# Sheet1.net
KiCad netlist of a schematic drawn in Altium Designer
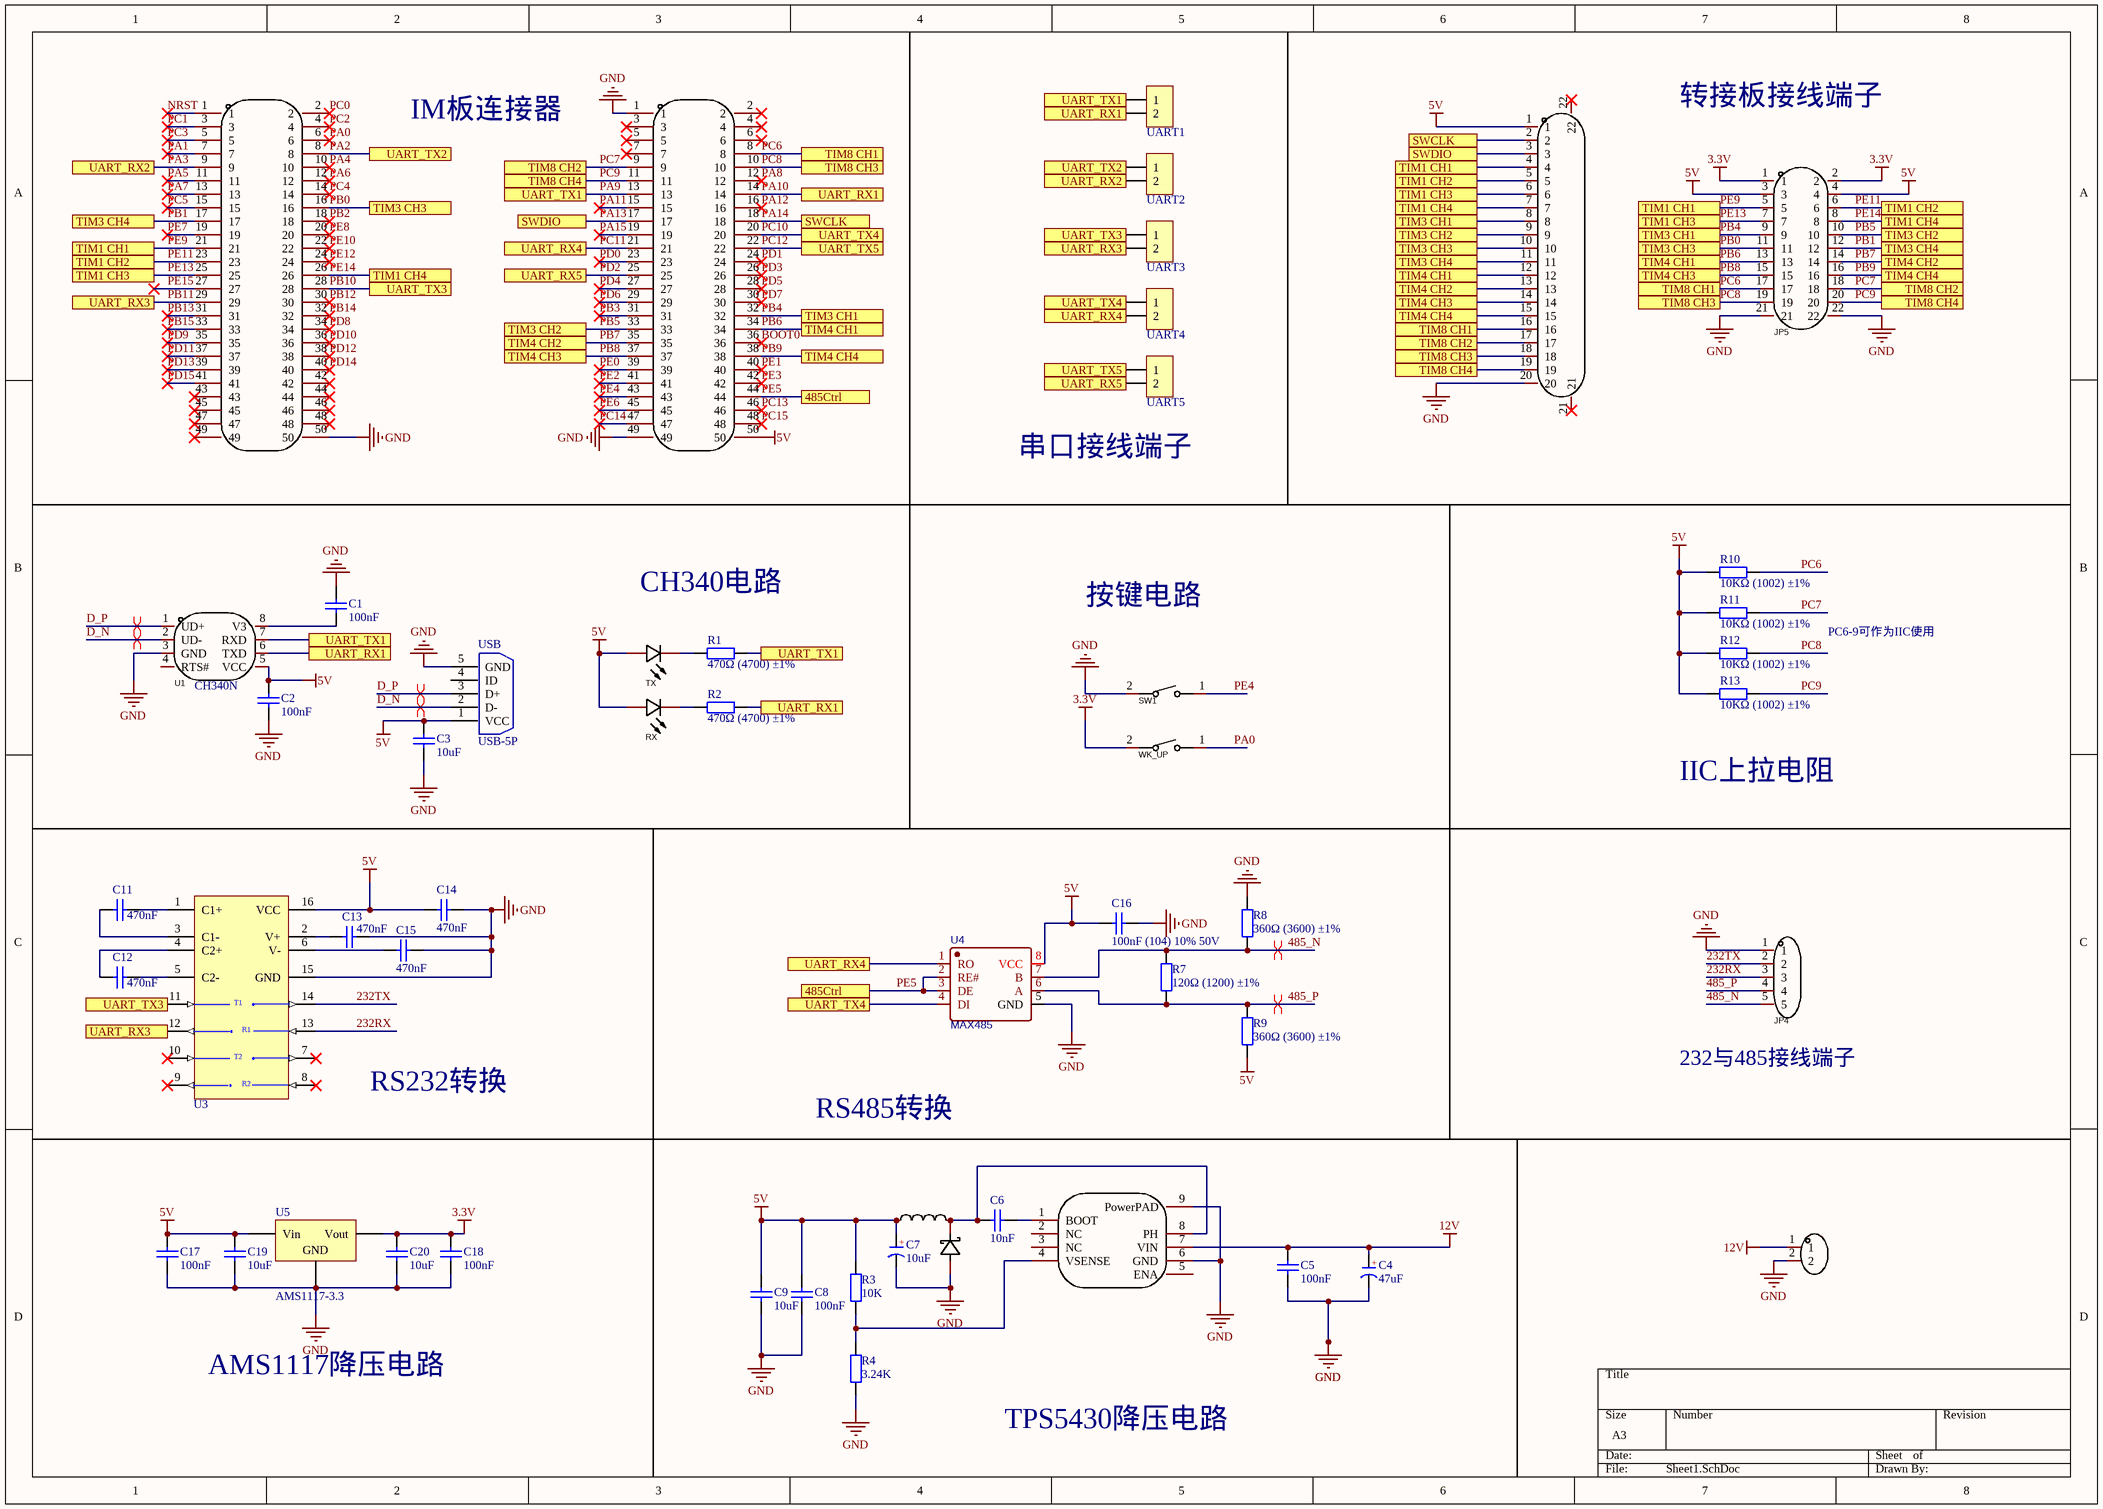
[diagram p0: Sheet1.SchDoc]

(export (version "E")
  (design (tool "Eeschema 10.0.6"))
  (components
    (comp (ref "C1")
      (value "100nF")
      (footprint "SIGMA:0603_C")
      (description "贴片电容")
      (libsource (lib "SIGMA") (part "0603 100nF (104) 10% 50V"))
    )
    (comp (ref "C2")
      (value "100nF")
      (footprint "SIGMA:0603_C")
      (description "贴片电容")
      (libsource (lib "SIGMA") (part "0603 100nF (104) 10% 50V"))
    )
    (comp (ref "C3")
      (value "10uF")
      (footprint "SIGMA:0603_C")
      (description "贴片电容")
      (libsource (lib "SIGMA") (part "0603 10uF (106) 10% 10V"))
    )
    (comp (ref "C4")
      (value "47uF")
      (footprint "SIGMA:CM D(6.3*5.4)")
      (description "贴片电解电容")
      (fields (field (name "版权归属") "源创客"))
      (libsource (lib "SIGMA") (part "C-CM"))
    )
    (comp (ref "C5")
      (value "100nF")
      (footprint "SIGMA:0603_C")
      (description "贴片电容")
      (libsource (lib "SIGMA") (part "0603 100nF (104) 10% 50V"))
    )
    (comp (ref "C6")
      (value "10nF")
      (footprint "SIGMA:0603_C")
      (description "贴片电容")
      (libsource (lib "SIGMA") (part "0603 10nF (103) 10% 50V"))
    )
    (comp (ref "C7")
      (value "10uF")
      (footprint "SIGMA:CM B(4*5.4)")
      (description "贴片电解电容")
      (fields (field (name "版权归属") "源创客"))
      (libsource (lib "SIGMA") (part "C-CM"))
    )
    (comp (ref "C8")
      (value "100nF")
      (footprint "SIGMA:0603_C")
      (description "贴片电容")
      (libsource (lib "SIGMA") (part "0603 100nF (104) 10% 50V"))
    )
    (comp (ref "C9")
      (value "10uF")
      (footprint "SIGMA:0603_C")
      (description "贴片电容")
      (libsource (lib "SIGMA") (part "0603 10uF (106) 10% 10V"))
    )
    (comp (ref "C11")
      (value "470nF")
      (footprint "SIGMA:0603_C")
      (description "贴片电容")
      (libsource (lib "2-Cap") (part "0603 100nF (104) 10% 50V"))
    )
    (comp (ref "C12")
      (value "470nF")
      (footprint "SIGMA:0603_C")
      (description "贴片电容")
      (libsource (lib "2-Cap") (part "0603 100nF (104) 10% 50V"))
    )
    (comp (ref "C13")
      (value "470nF")
      (footprint "SIGMA:0603_C")
      (description "贴片电容")
      (libsource (lib "2-Cap") (part "0603 100nF (104) 10% 50V"))
    )
    (comp (ref "C14")
      (value "470nF")
      (footprint "SIGMA:0603_C")
      (description "贴片电容")
      (libsource (lib "2-Cap") (part "0603 100nF (104) 10% 50V"))
    )
    (comp (ref "C15")
      (value "470nF")
      (footprint "SIGMA:0603_C")
      (description "贴片电容")
      (libsource (lib "2-Cap") (part "0603 100nF (104) 10% 50V"))
    )
    (comp (ref "C16")
      (value "100nF (104) 10% 50V")
      (footprint "SIGMA:0603_C")
      (description "贴片电容")
      (libsource (lib "2-Cap") (part "0603 100nF (104) 10% 50V"))
    )
    (comp (ref "C17")
      (value "100nF")
      (footprint "SIGMA:0603_C")
      (description "贴片电容")
      (libsource (lib "SIGMA") (part "0603 100nF (104) 10% 50V"))
    )
    (comp (ref "C18")
      (value "100nF")
      (footprint "SIGMA:0603_C")
      (description "贴片电容")
      (libsource (lib "SIGMA") (part "0603 100nF (104) 10% 50V"))
    )
    (comp (ref "C19")
      (value "10uF")
      (footprint "SIGMA:0603_C")
      (description "贴片电容")
      (libsource (lib "SIGMA") (part "0603 10uF (106) 10% 10V"))
    )
    (comp (ref "C20")
      (value "10uF")
      (footprint "SIGMA:0603_C")
      (description "贴片电容")
      (libsource (lib "SIGMA") (part "0603 10uF (106) 10% 10V"))
    )
    (comp (ref "D1")
      (value "SS54_C2988643")
      (footprint "SMB_L4.3-W3.6-LS5.4-RD")
      (fields (field (name "MANUFACTURER") "UMW(广东友台半导体)") (field (name "MANUFACTURER PART") "SS54"))
      (libsource (lib "LC_Components") (part "SS54_C2988643"))
    )
    (comp (ref "FPC1")
      (value "FPC-05F-20PH20")
      (footprint "FPC-SMD_20P-P0.50_XUNPU_FPC-05F-20PH20")
      (fields (field (name "MANUFACTURER") "XUNPU(讯普)"))
      (libsource (lib "LC_Components") (part "FPC-05F-20PH20"))
    )
    (comp (ref "JP1")
      (value "2685Y-225CNG1SNA01")
      (footprint "HDR-TH_50P-P2.54-V-F-R2-C25-S2.54-1")
      (fields (field (name "MANUFACTURER") "华宇创"))
      (libsource (lib "LC_Components") (part "2685Y-225CNG1SNA01"))
    )
    (comp (ref "JP2")
      (value "2685Y-225CNG1SNA01")
      (footprint "HDR-TH_50P-P2.54-V-F-R2-C25-S2.54-1")
      (fields (field (name "MANUFACTURER") "华宇创"))
      (libsource (lib "LC_Components") (part "2685Y-225CNG1SNA01"))
    )
    (comp (ref "JP3")
      (value "KF2EDGR-3.81-2P")
      (footprint "CONN-TH_2P-P3.81_KF2EDGR-3.81-2P")
      (fields (field (name "MANUFACTURER") "KEFA(科发)"))
      (libsource (lib "LC_Components") (part "KF2EDGR-3.81-2P"))
    )
    (comp (ref "JP4")
      (value "KF2EDGR-3.5-5P")
      (footprint "CONN-TH_5P-P3.50_KF2EDGR-3.5-5P")
      (fields (field (name "MANUFACTURER") "KEFA(科发)"))
      (libsource (lib "LC_Components") (part "KF2EDGR-3.5-5P"))
    )
    (comp (ref "JP5")
      (value "PZ254V-12-22P")
      (footprint "HDR-TH_22P-P2.54-V-M-R2-C11-S2.54")
      (description "HDR2.54 2x11P")
      (fields (field (name "MANUFACTURER") "XFCN(兴飞)"))
      (libsource (lib "LC_Components") (part "PZ254V-12-22P"))
    )
    (comp (ref "L1")
      (value "MWSA0603S-220MT")
      (footprint "IND-SMD_L7.3-W6.8")
      (description "22uH")
      (fields (field (name "MANUFACTURER") "Sunlord(顺络)") (field (name "TOLERANCE") "±20%"))
      (libsource (lib "LC_Components") (part "MWSA0603S-220MT"))
    )
    (comp (ref "R1")
      (value "470Ω (4700) ±1%")
      (footprint "SIGMA:0603_R")
      (description "贴片电阻")
      (libsource (lib "SIGMA") (part "0603 470Ω (4700) 1%"))
    )
    (comp (ref "R2")
      (value "470Ω (4700) ±1%")
      (footprint "SIGMA:0603_R")
      (description "贴片电阻")
      (libsource (lib "SIGMA") (part "0603 470Ω (4700) 1%"))
    )
    (comp (ref "R3")
      (value "10K")
      (footprint "SIGMA:0603_R")
      (description "贴片电阻")
      (libsource (lib "SIGMA") (part "0603 1.1KΩ (1101) 1%"))
    )
    (comp (ref "R4")
      (value "3.24K")
      (footprint "SIGMA:0603_R")
      (description "贴片电阻")
      (libsource (lib "SIGMA") (part "0603 1.1KΩ (1101) 1%"))
    )
    (comp (ref "R7")
      (value "120Ω (1200) ±1%")
      (footprint "SIGMA:0603_R")
      (description "贴片电阻")
      (libsource (lib "1-RES") (part "0603 120Ω (1200) 1%"))
    )
    (comp (ref "R8")
      (value "360Ω (3600) ±1%")
      (footprint "SIGMA:0603_R")
      (description "贴片电阻")
      (libsource (lib "1-RES") (part "0603 360Ω (3600) 1%"))
    )
    (comp (ref "R9")
      (value "360Ω (3600) ±1%")
      (footprint "SIGMA:0603_R")
      (description "贴片电阻")
      (libsource (lib "1-RES") (part "0603 360Ω (3600) 1%"))
    )
    (comp (ref "R10")
      (value "10KΩ (1002) ±1%")
      (footprint "SIGMA:0603_R")
      (description "贴片电阻")
      (libsource (lib "SIGMA") (part "0603 10KΩ (1002) 1%"))
    )
    (comp (ref "R11")
      (value "10KΩ (1002) ±1%")
      (footprint "SIGMA:0603_R")
      (description "贴片电阻")
      (libsource (lib "SIGMA") (part "0603 10KΩ (1002) 1%"))
    )
    (comp (ref "R12")
      (value "10KΩ (1002) ±1%")
      (footprint "SIGMA:0603_R")
      (description "贴片电阻")
      (libsource (lib "SIGMA") (part "0603 10KΩ (1002) 1%"))
    )
    (comp (ref "R13")
      (value "10KΩ (1002) ±1%")
      (footprint "SIGMA:0603_R")
      (description "贴片电阻")
      (libsource (lib "SIGMA") (part "0603 10KΩ (1002) 1%"))
    )
    (comp (ref "RX")
      (value "NCD0603R1_C84263")
      (footprint "LED0603-RD")
      (fields (field (name "MANUFACTURER") "国星光电") (field (name "MANUFACTURER PART") "NCD0603R1"))
      (libsource (lib "SIGMA") (part "0603 LED-RD"))
    )
    (comp (ref "SW1")
      (value "TS3625A-HT")
      (footprint "SW-SMD_L6.1-W3.7-LS7.9")
      (description "红头按键")
      (fields (field (name "MANUFACTURER") "SHOU HAN(首韩)"))
      (libsource (lib "LC_Components") (part "TS3625A-HT"))
    )
    (comp (ref "TX")
      (value "NCD0603R1_C84263")
      (footprint "LED0603-RD")
      (fields (field (name "MANUFACTURER") "国星光电") (field (name "MANUFACTURER PART") "NCD0603R1"))
      (libsource (lib "SIGMA") (part "0603 LED-RD"))
    )
    (comp (ref "U1")
      (value "CH340N")
      (footprint "SOP-8_L4.9-W3.9-P1.27-LS6.0-BL")
      (fields (field (name "DESIGNER") "U?"))
      (libsource (lib "LC_Components") (part "CH340N_C2977777"))
    )
    (comp (ref "U3")
      (value "MAX232IDR C18261")
      (footprint "SIGMA:SOIC-16_150mil")
      (description "+3.3V Powered, Multi-Channel RS-232 Driver/Receiver")
      (fields (field (name "PUBLISHER") "Altium Limited"))
      (libsource (lib "SIGMA") (part "MAX3232IDR C18261"))
    )
    (comp (ref "U4")
      (value "MAX485")
      (footprint "SIGMA:SOIC-8_150MIL")
      (description "485芯片")
      (fields
        (field (name "BOM_MANUFACTURER PART") "MAX3485ESA+T")
        (field (name "BOM_SUPPLIER PART") "C18148")
      )
      (libsource (lib "SIGMA") (part "MAX3485ESA+T C18148"))
    )
    (comp (ref "U5")
      (value "AMS1117-3.3")
      (footprint "SIGMA:SOT-223")
      (description "低压差线性稳压(LDO)")
      (libsource (lib "SIGMA") (part "SOT-223 AMS1117-3.3"))
    )
    (comp (ref "U6")
      (value "TPS5430DDAR")
      (footprint "ESOP-8_L4.9-W3.9-P1.27-LS6.0-TL-EP")
      (fields (field (name "MANUFACTURER") "TI(德州仪器)"))
      (libsource (lib "LC_Components") (part "TPS5430DDAR"))
    )
    (comp (ref "UART1")
      (value "HDR-1X2")
      (footprint "SIGMA:XH2.54-WI-2P")
      (description "2P接插件")
      (fields (field (name "版权归属") "源创客"))
      (libsource (lib "12-Connector") (part "Header 2 Pitch2.54"))
    )
    (comp (ref "UART2")
      (value "HDR-1X2")
      (footprint "SIGMA:XH2.54-WI-2P")
      (description "2P接插件")
      (fields (field (name "版权归属") "源创客"))
      (libsource (lib "12-Connector") (part "Header 2 Pitch2.54"))
    )
    (comp (ref "UART3")
      (value "HDR-1X2")
      (footprint "SIGMA:XH2.54-WI-2P")
      (description "2P接插件")
      (fields (field (name "版权归属") "源创客"))
      (libsource (lib "12-Connector") (part "Header 2 Pitch2.54"))
    )
    (comp (ref "UART4")
      (value "HDR-1X2")
      (footprint "SIGMA:XH2.54-WI-2P")
      (description "2P接插件")
      (fields (field (name "版权归属") "源创客"))
      (libsource (lib "12-Connector") (part "Header 2 Pitch2.54"))
    )
    (comp (ref "UART5")
      (value "HDR-1X2")
      (footprint "SIGMA:XH2.54-WI-2P")
      (description "2P接插件")
      (fields (field (name "版权归属") "源创客"))
      (libsource (lib "12-Connector") (part "Header 2 Pitch2.54"))
    )
    (comp (ref "USB")
      (value "USB-5P")
      (footprint "USB-MINI-A")
      (description "微型USB母座")
      (fields (field (name "版权归属") "源创客"))
      (libsource (lib "IMX6UL_ALPHA(底板)_V2.0") (part "USB-5P"))
    )
    (comp (ref "WK_UP")
      (value "TS3625A-HT")
      (footprint "SW-SMD_L6.1-W3.7-LS7.9")
      (description "红头按键")
      (fields (field (name "MANUFACTURER") "SHOU HAN(首韩)"))
      (libsource (lib "LC_Components") (part "TS3625A-HT"))
    )
  )
  (nets
    (net (code "1") (name "/232RX") (class "Default")
      (node (ref "JP4") (pin "3") (pinfunction "3_3") (pintype "passive"))
      (node (ref "U3") (pin "13") (pinfunction "R1IN_13") (pintype "input"))
    )
    (net (code "2") (name "/232TX") (class "Default")
      (node (ref "JP4") (pin "2") (pinfunction "2_2") (pintype "passive"))
      (node (ref "U3") (pin "14") (pinfunction "T1OUT_14") (pintype "output"))
    )
    (net (code "3") (name "/485_N") (class "Default")
      (node (ref "JP4") (pin "5") (pinfunction "5_5") (pintype "passive"))
      (node (ref "R7") (pin "2") (pinfunction "2_2") (pintype "passive"))
      (node (ref "R8") (pin "1") (pinfunction "1_1") (pintype "passive"))
      (node (ref "U4") (pin "7") (pinfunction "B_7") (pintype "passive"))
    )
    (net (code "4") (name "/485_P") (class "Default")
      (node (ref "JP4") (pin "4") (pinfunction "4_4") (pintype "passive"))
      (node (ref "R7") (pin "1") (pinfunction "1_1") (pintype "passive"))
      (node (ref "R9") (pin "2") (pinfunction "2_2") (pintype "passive"))
      (node (ref "U4") (pin "6") (pinfunction "A_6") (pintype "passive"))
    )
    (net (code "5") (name "/BOOT0") (class "Default")
      (node (ref "JP2") (pin "36") (pinfunction "36_36") (pintype "passive+no_connect"))
    )
    (net (code "6") (name "/D_N") (class "Default")
      (node (ref "U1") (pin "2") (pinfunction "UD-_2") (pintype "passive"))
      (node (ref "USB") (pin "2") (pinfunction "D-_2") (pintype "passive"))
    )
    (net (code "7") (name "/D_P") (class "Default")
      (node (ref "U1") (pin "1") (pinfunction "UD+_1") (pintype "passive"))
      (node (ref "USB") (pin "3") (pinfunction "D+_3") (pintype "passive"))
    )
    (net (code "8") (name "/NRST") (class "Default")
      (node (ref "JP1") (pin "1") (pinfunction "1_1") (pintype "passive+no_connect"))
    )
    (net (code "9") (name "/PA0") (class "Default")
      (node (ref "JP1") (pin "6") (pinfunction "6_6") (pintype "passive"))
      (node (ref "WK_UP") (pin "1") (pinfunction "A_1") (pintype "passive"))
    )
    (net (code "10") (name "/PA1") (class "Default")
      (node (ref "JP1") (pin "7") (pinfunction "7_7") (pintype "passive+no_connect"))
    )
    (net (code "11") (name "/PA2") (class "Default")
      (node (ref "JP1") (pin "8") (pinfunction "8_8") (pintype "passive"))
      (node (ref "UART2") (pin "1") (pinfunction "1_1") (pintype "passive"))
    )
    (net (code "12") (name "/PA3") (class "Default")
      (node (ref "JP1") (pin "9") (pinfunction "9_9") (pintype "passive"))
      (node (ref "UART2") (pin "2") (pinfunction "2_2") (pintype "passive"))
    )
    (net (code "13") (name "/PA4") (class "Default")
      (node (ref "JP1") (pin "10") (pinfunction "10_10") (pintype "passive+no_connect"))
    )
    (net (code "14") (name "/PA5") (class "Default")
      (node (ref "JP1") (pin "11") (pinfunction "11_11") (pintype "passive+no_connect"))
    )
    (net (code "15") (name "/PA6") (class "Default")
      (node (ref "JP1") (pin "12") (pinfunction "12_12") (pintype "passive+no_connect"))
    )
    (net (code "16") (name "/PA7") (class "Default")
      (node (ref "JP1") (pin "13") (pinfunction "13_13") (pintype "passive+no_connect"))
    )
    (net (code "17") (name "/PA8") (class "Default")
      (node (ref "JP2") (pin "12") (pinfunction "12_12") (pintype "passive+no_connect"))
    )
    (net (code "18") (name "/PA9") (class "Default")
      (node (ref "JP2") (pin "13") (pinfunction "13_13") (pintype "passive"))
      (node (ref "R1") (pin "2") (pinfunction "2_2") (pintype "passive"))
      (node (ref "U1") (pin "7") (pinfunction "RXD_7") (pintype "passive"))
      (node (ref "UART1") (pin "1") (pinfunction "1_1") (pintype "passive"))
    )
    (net (code "19") (name "/PA10") (class "Default")
      (node (ref "JP2") (pin "14") (pinfunction "14_14") (pintype "passive"))
      (node (ref "R2") (pin "2") (pinfunction "2_2") (pintype "passive"))
      (node (ref "U1") (pin "6") (pinfunction "TXD_6") (pintype "passive"))
      (node (ref "UART1") (pin "2") (pinfunction "2_2") (pintype "passive"))
    )
    (net (code "20") (name "/PA11") (class "Default")
      (node (ref "JP2") (pin "15") (pinfunction "15_15") (pintype "passive+no_connect"))
    )
    (net (code "21") (name "/PA12") (class "Default")
      (node (ref "JP2") (pin "16") (pinfunction "16_16") (pintype "passive+no_connect"))
    )
    (net (code "22") (name "/PA13") (class "Default")
      (node (ref "FPC1") (pin "3") (pinfunction "3_3") (pintype "passive"))
      (node (ref "JP2") (pin "17") (pinfunction "17_17") (pintype "passive"))
    )
    (net (code "23") (name "/PA14") (class "Default")
      (node (ref "FPC1") (pin "2") (pinfunction "2_2") (pintype "passive"))
      (node (ref "JP2") (pin "18") (pinfunction "18_18") (pintype "passive"))
    )
    (net (code "24") (name "/PA15") (class "Default")
      (node (ref "JP2") (pin "19") (pinfunction "19_19") (pintype "passive+no_connect"))
    )
    (net (code "25") (name "/PB0") (class "Default")
      (node (ref "FPC1") (pin "10") (pinfunction "10_10") (pintype "passive"))
      (node (ref "JP1") (pin "16") (pinfunction "16_16") (pintype "passive"))
      (node (ref "JP5") (pin "11") (pinfunction "11_11") (pintype "passive"))
    )
    (net (code "26") (name "/PB1") (class "Default")
      (node (ref "FPC1") (pin "11") (pinfunction "11_11") (pintype "passive"))
      (node (ref "JP1") (pin "17") (pinfunction "17_17") (pintype "passive"))
      (node (ref "JP5") (pin "12") (pinfunction "12_12") (pintype "passive"))
    )
    (net (code "27") (name "/PB2") (class "Default")
      (node (ref "JP1") (pin "18") (pinfunction "18_18") (pintype "passive+no_connect"))
    )
    (net (code "28") (name "/PB3") (class "Default")
      (node (ref "JP2") (pin "31") (pinfunction "31_31") (pintype "passive+no_connect"))
    )
    (net (code "29") (name "/PB4") (class "Default")
      (node (ref "FPC1") (pin "8") (pinfunction "8_8") (pintype "passive"))
      (node (ref "JP2") (pin "32") (pinfunction "32_32") (pintype "passive"))
      (node (ref "JP5") (pin "9") (pinfunction "9_9") (pintype "passive"))
    )
    (net (code "30") (name "/PB5") (class "Default")
      (node (ref "FPC1") (pin "9") (pinfunction "9_9") (pintype "passive"))
      (node (ref "JP2") (pin "33") (pinfunction "33_33") (pintype "passive"))
      (node (ref "JP5") (pin "10") (pinfunction "10_10") (pintype "passive"))
    )
    (net (code "31") (name "/PB6") (class "Default")
      (node (ref "FPC1") (pin "12") (pinfunction "12_12") (pintype "passive"))
      (node (ref "JP2") (pin "34") (pinfunction "34_34") (pintype "passive"))
      (node (ref "JP5") (pin "13") (pinfunction "13_13") (pintype "passive"))
    )
    (net (code "32") (name "/PB7") (class "Default")
      (node (ref "FPC1") (pin "13") (pinfunction "13_13") (pintype "passive"))
      (node (ref "JP2") (pin "35") (pinfunction "35_35") (pintype "passive"))
      (node (ref "JP5") (pin "14") (pinfunction "14_14") (pintype "passive"))
    )
    (net (code "33") (name "/PB8") (class "Default")
      (node (ref "FPC1") (pin "14") (pinfunction "14_14") (pintype "passive"))
      (node (ref "JP2") (pin "37") (pinfunction "37_37") (pintype "passive"))
      (node (ref "JP5") (pin "15") (pinfunction "15_15") (pintype "passive"))
    )
    (net (code "34") (name "/PB9") (class "Default")
      (node (ref "FPC1") (pin "15") (pinfunction "15_15") (pintype "passive"))
      (node (ref "JP2") (pin "38") (pinfunction "38_38") (pintype "passive"))
      (node (ref "JP5") (pin "16") (pinfunction "16_16") (pintype "passive"))
    )
    (net (code "35") (name "/PB10") (class "Default")
      (node (ref "JP1") (pin "28") (pinfunction "28_28") (pintype "passive"))
      (node (ref "U3") (pin "11") (pinfunction "T1IN_11") (pintype "input"))
      (node (ref "UART3") (pin "1") (pinfunction "1_1") (pintype "passive"))
    )
    (net (code "36") (name "/PB11") (class "Default")
      (node (ref "JP1") (pin "29") (pinfunction "29_29") (pintype "passive"))
      (node (ref "U3") (pin "12") (pinfunction "R1OUT_12") (pintype "output"))
      (node (ref "UART3") (pin "2") (pinfunction "2_2") (pintype "passive"))
    )
    (net (code "37") (name "/PB12") (class "Default")
      (node (ref "JP1") (pin "30") (pinfunction "30_30") (pintype "passive+no_connect"))
    )
    (net (code "38") (name "/PB13") (class "Default")
      (node (ref "JP1") (pin "31") (pinfunction "31_31") (pintype "passive+no_connect"))
    )
    (net (code "39") (name "/PB14") (class "Default")
      (node (ref "JP1") (pin "32") (pinfunction "32_32") (pintype "passive+no_connect"))
    )
    (net (code "40") (name "/PB15") (class "Default")
      (node (ref "JP1") (pin "33") (pinfunction "33_33") (pintype "passive+no_connect"))
    )
    (net (code "41") (name "/PC0") (class "Default")
      (node (ref "JP1") (pin "2") (pinfunction "2_2") (pintype "passive+no_connect"))
    )
    (net (code "42") (name "/PC1") (class "Default")
      (node (ref "JP1") (pin "3") (pinfunction "3_3") (pintype "passive+no_connect"))
    )
    (net (code "43") (name "/PC2") (class "Default")
      (node (ref "JP1") (pin "4") (pinfunction "4_4") (pintype "passive+no_connect"))
    )
    (net (code "44") (name "/PC3") (class "Default")
      (node (ref "JP1") (pin "5") (pinfunction "5_5") (pintype "passive+no_connect"))
    )
    (net (code "45") (name "/PC4") (class "Default")
      (node (ref "JP1") (pin "14") (pinfunction "14_14") (pintype "passive+no_connect"))
    )
    (net (code "46") (name "/PC5") (class "Default")
      (node (ref "JP1") (pin "15") (pinfunction "15_15") (pintype "passive+no_connect"))
    )
    (net (code "47") (name "/PC6") (class "Default")
      (node (ref "FPC1") (pin "16") (pinfunction "16_16") (pintype "passive"))
      (node (ref "JP2") (pin "8") (pinfunction "8_8") (pintype "passive"))
      (node (ref "JP5") (pin "17") (pinfunction "17_17") (pintype "passive"))
      (node (ref "R10") (pin "2") (pinfunction "2_2") (pintype "passive"))
    )
    (net (code "48") (name "/PC7") (class "Default")
      (node (ref "FPC1") (pin "17") (pinfunction "17_17") (pintype "passive"))
      (node (ref "JP2") (pin "9") (pinfunction "9_9") (pintype "passive"))
      (node (ref "JP5") (pin "18") (pinfunction "18_18") (pintype "passive"))
      (node (ref "R11") (pin "2") (pinfunction "2_2") (pintype "passive"))
    )
    (net (code "49") (name "/PC8") (class "Default")
      (node (ref "FPC1") (pin "18") (pinfunction "18_18") (pintype "passive"))
      (node (ref "JP2") (pin "10") (pinfunction "10_10") (pintype "passive"))
      (node (ref "JP5") (pin "19") (pinfunction "19_19") (pintype "passive"))
      (node (ref "R12") (pin "2") (pinfunction "2_2") (pintype "passive"))
    )
    (net (code "50") (name "/PC9") (class "Default")
      (node (ref "FPC1") (pin "19") (pinfunction "19_19") (pintype "passive"))
      (node (ref "JP2") (pin "11") (pinfunction "11_11") (pintype "passive"))
      (node (ref "JP5") (pin "20") (pinfunction "20_20") (pintype "passive"))
      (node (ref "R13") (pin "2") (pinfunction "2_2") (pintype "passive"))
    )
    (net (code "51") (name "/PC10") (class "Default")
      (node (ref "JP2") (pin "20") (pinfunction "20_20") (pintype "passive"))
      (node (ref "U4") (pin "4") (pinfunction "DI_4") (pintype "passive"))
      (node (ref "UART4") (pin "1") (pinfunction "1_1") (pintype "passive"))
    )
    (net (code "52") (name "/PC11") (class "Default")
      (node (ref "JP2") (pin "21") (pinfunction "21_21") (pintype "passive"))
      (node (ref "U4") (pin "1") (pinfunction "RO_1") (pintype "passive"))
      (node (ref "UART4") (pin "2") (pinfunction "2_2") (pintype "passive"))
    )
    (net (code "53") (name "/PC12") (class "Default")
      (node (ref "JP2") (pin "22") (pinfunction "22_22") (pintype "passive"))
      (node (ref "UART5") (pin "1") (pinfunction "1_1") (pintype "passive"))
    )
    (net (code "54") (name "/PC13") (class "Default")
      (node (ref "JP2") (pin "46") (pinfunction "46_46") (pintype "passive+no_connect"))
    )
    (net (code "55") (name "/PC14") (class "Default")
      (node (ref "JP2") (pin "47") (pinfunction "47_47") (pintype "passive+no_connect"))
    )
    (net (code "56") (name "/PC15") (class "Default")
      (node (ref "JP2") (pin "48") (pinfunction "48_48") (pintype "passive+no_connect"))
    )
    (net (code "57") (name "/PD0") (class "Default")
      (node (ref "JP2") (pin "23") (pinfunction "23_23") (pintype "passive+no_connect"))
    )
    (net (code "58") (name "/PD1") (class "Default")
      (node (ref "JP2") (pin "24") (pinfunction "24_24") (pintype "passive+no_connect"))
    )
    (net (code "59") (name "/PD2") (class "Default")
      (node (ref "JP2") (pin "25") (pinfunction "25_25") (pintype "passive"))
      (node (ref "UART5") (pin "2") (pinfunction "2_2") (pintype "passive"))
    )
    (net (code "60") (name "/PD3") (class "Default")
      (node (ref "JP2") (pin "26") (pinfunction "26_26") (pintype "passive+no_connect"))
    )
    (net (code "61") (name "/PD4") (class "Default")
      (node (ref "JP2") (pin "27") (pinfunction "27_27") (pintype "passive+no_connect"))
    )
    (net (code "62") (name "/PD5") (class "Default")
      (node (ref "JP2") (pin "28") (pinfunction "28_28") (pintype "passive+no_connect"))
    )
    (net (code "63") (name "/PD6") (class "Default")
      (node (ref "JP2") (pin "29") (pinfunction "29_29") (pintype "passive+no_connect"))
    )
    (net (code "64") (name "/PD7") (class "Default")
      (node (ref "JP2") (pin "30") (pinfunction "30_30") (pintype "passive+no_connect"))
    )
    (net (code "65") (name "/PD8") (class "Default")
      (node (ref "JP1") (pin "34") (pinfunction "34_34") (pintype "passive+no_connect"))
    )
    (net (code "66") (name "/PD9") (class "Default")
      (node (ref "JP1") (pin "35") (pinfunction "35_35") (pintype "passive+no_connect"))
    )
    (net (code "67") (name "/PD10") (class "Default")
      (node (ref "JP1") (pin "36") (pinfunction "36_36") (pintype "passive+no_connect"))
    )
    (net (code "68") (name "/PD11") (class "Default")
      (node (ref "JP1") (pin "37") (pinfunction "37_37") (pintype "passive+no_connect"))
    )
    (net (code "69") (name "/PD12") (class "Default")
      (node (ref "JP1") (pin "38") (pinfunction "38_38") (pintype "passive+no_connect"))
    )
    (net (code "70") (name "/PD13") (class "Default")
      (node (ref "JP1") (pin "39") (pinfunction "39_39") (pintype "passive+no_connect"))
    )
    (net (code "71") (name "/PD14") (class "Default")
      (node (ref "JP1") (pin "40") (pinfunction "40_40") (pintype "passive+no_connect"))
    )
    (net (code "72") (name "/PD15") (class "Default")
      (node (ref "JP1") (pin "41") (pinfunction "41_41") (pintype "passive+no_connect"))
    )
    (net (code "73") (name "/PE0") (class "Default")
      (node (ref "JP2") (pin "39") (pinfunction "39_39") (pintype "passive+no_connect"))
    )
    (net (code "74") (name "/PE1") (class "Default")
      (node (ref "JP2") (pin "40") (pinfunction "40_40") (pintype "passive+no_connect"))
    )
    (net (code "75") (name "/PE2") (class "Default")
      (node (ref "JP2") (pin "41") (pinfunction "41_41") (pintype "passive+no_connect"))
    )
    (net (code "76") (name "/PE3") (class "Default")
      (node (ref "JP2") (pin "42") (pinfunction "42_42") (pintype "passive+no_connect"))
    )
    (net (code "77") (name "/PE4") (class "Default")
      (node (ref "JP2") (pin "43") (pinfunction "43_43") (pintype "passive"))
      (node (ref "SW1") (pin "1") (pinfunction "A_1") (pintype "passive"))
    )
    (net (code "78") (name "/PE5") (class "Default")
      (node (ref "JP2") (pin "44") (pinfunction "44_44") (pintype "passive"))
      (node (ref "U4") (pin "2") (pinfunction "RE#_2") (pintype "passive"))
      (node (ref "U4") (pin "3") (pinfunction "DE_3") (pintype "passive"))
    )
    (net (code "79") (name "/PE6") (class "Default")
      (node (ref "JP2") (pin "45") (pinfunction "45_45") (pintype "passive+no_connect"))
    )
    (net (code "80") (name "/PE7") (class "Default")
      (node (ref "JP1") (pin "19") (pinfunction "19_19") (pintype "passive+no_connect"))
    )
    (net (code "81") (name "/PE8") (class "Default")
      (node (ref "JP1") (pin "20") (pinfunction "20_20") (pintype "passive+no_connect"))
    )
    (net (code "82") (name "/PE9") (class "Default")
      (node (ref "FPC1") (pin "4") (pinfunction "4_4") (pintype "passive"))
      (node (ref "JP1") (pin "21") (pinfunction "21_21") (pintype "passive"))
      (node (ref "JP5") (pin "5") (pinfunction "5_5") (pintype "passive"))
    )
    (net (code "83") (name "/PE10") (class "Default")
      (node (ref "JP1") (pin "22") (pinfunction "22_22") (pintype "passive+no_connect"))
    )
    (net (code "84") (name "/PE11") (class "Default")
      (node (ref "FPC1") (pin "5") (pinfunction "5_5") (pintype "passive"))
      (node (ref "JP1") (pin "23") (pinfunction "23_23") (pintype "passive"))
      (node (ref "JP5") (pin "6") (pinfunction "6_6") (pintype "passive"))
    )
    (net (code "85") (name "/PE12") (class "Default")
      (node (ref "JP1") (pin "24") (pinfunction "24_24") (pintype "passive+no_connect"))
    )
    (net (code "86") (name "/PE13") (class "Default")
      (node (ref "FPC1") (pin "6") (pinfunction "6_6") (pintype "passive"))
      (node (ref "JP1") (pin "25") (pinfunction "25_25") (pintype "passive"))
      (node (ref "JP5") (pin "7") (pinfunction "7_7") (pintype "passive"))
    )
    (net (code "87") (name "/PE14") (class "Default")
      (node (ref "FPC1") (pin "7") (pinfunction "7_7") (pintype "passive"))
      (node (ref "JP1") (pin "26") (pinfunction "26_26") (pintype "passive"))
      (node (ref "JP5") (pin "8") (pinfunction "8_8") (pintype "passive"))
    )
    (net (code "88") (name "/PE15") (class "Default")
      (node (ref "JP1") (pin "27") (pinfunction "27_27") (pintype "passive+no_connect"))
    )
    (net (code "89") (name "3.3V") (class "Default")
      (node (ref "C18") (pin "2") (pinfunction "2_2") (pintype "passive"))
      (node (ref "C20") (pin "2") (pinfunction "2_2") (pintype "passive"))
      (node (ref "JP5") (pin "1") (pinfunction "1_1") (pintype "passive"))
      (node (ref "JP5") (pin "2") (pinfunction "2_2") (pintype "passive"))
      (node (ref "U5") (pin "2") (pinfunction "Vout_2") (pintype "passive"))
      (node (ref "WK_UP") (pin "2") (pinfunction "B_2") (pintype "passive"))
    )
    (net (code "90") (name "5V") (class "Default")
      (node (ref "C14") (pin "1") (pinfunction "1_1") (pintype "passive"))
      (node (ref "C16") (pin "1") (pinfunction "1_1") (pintype "passive"))
      (node (ref "C17") (pin "2") (pinfunction "2_2") (pintype "passive"))
      (node (ref "C19") (pin "2") (pinfunction "2_2") (pintype "passive"))
      (node (ref "C2") (pin "2") (pinfunction "2_2") (pintype "passive"))
      (node (ref "C3") (pin "2") (pinfunction "2_2") (pintype "passive"))
      (node (ref "C7") (pin "1") (pinfunction "A_1") (pintype "passive"))
      (node (ref "C8") (pin "2") (pinfunction "2_2") (pintype "passive"))
      (node (ref "C9") (pin "2") (pinfunction "2_2") (pintype "passive"))
      (node (ref "FPC1") (pin "1") (pinfunction "1_1") (pintype "passive"))
      (node (ref "JP2") (pin "50") (pinfunction "50_50") (pintype "passive"))
      (node (ref "JP5") (pin "3") (pinfunction "3_3") (pintype "passive"))
      (node (ref "JP5") (pin "4") (pinfunction "4_4") (pintype "passive"))
      (node (ref "L1") (pin "1") (pinfunction "1_1") (pintype "passive"))
      (node (ref "R10") (pin "1") (pinfunction "1_1") (pintype "passive"))
      (node (ref "R11") (pin "1") (pinfunction "1_1") (pintype "passive"))
      (node (ref "R12") (pin "1") (pinfunction "1_1") (pintype "passive"))
      (node (ref "R13") (pin "1") (pinfunction "1_1") (pintype "passive"))
      (node (ref "R3") (pin "2") (pinfunction "2_2") (pintype "passive"))
      (node (ref "R9") (pin "1") (pinfunction "1_1") (pintype "passive"))
      (node (ref "RX") (pin "2") (pinfunction "A_2") (pintype "passive"))
      (node (ref "TX") (pin "2") (pinfunction "A_2") (pintype "passive"))
      (node (ref "U1") (pin "5") (pinfunction "VCC_5") (pintype "passive"))
      (node (ref "U3") (pin "16") (pinfunction "VCC_16") (pintype "power_in"))
      (node (ref "U4") (pin "8") (pinfunction "VCC_8") (pintype "passive"))
      (node (ref "U5") (pin "3") (pinfunction "Vin_3") (pintype "passive"))
      (node (ref "USB") (pin "1") (pinfunction "VCC_1") (pintype "passive"))
    )
    (net (code "91") (name "12V") (class "Default")
      (node (ref "C4") (pin "1") (pinfunction "A_1") (pintype "passive"))
      (node (ref "C5") (pin "2") (pinfunction "2_2") (pintype "passive"))
      (node (ref "JP3") (pin "1") (pinfunction "1_1") (pintype "passive"))
      (node (ref "U6") (pin "7") (pinfunction "VIN_7") (pintype "passive"))
    )
    (net (code "92") (name "GND") (class "Default")
      (node (ref "C1") (pin "1") (pinfunction "1_1") (pintype "passive"))
      (node (ref "C13") (pin "2") (pinfunction "2_2") (pintype "passive"))
      (node (ref "C14") (pin "2") (pinfunction "2_2") (pintype "passive"))
      (node (ref "C15") (pin "2") (pinfunction "2_2") (pintype "passive"))
      (node (ref "C16") (pin "2") (pinfunction "2_2") (pintype "passive"))
      (node (ref "C17") (pin "1") (pinfunction "1_1") (pintype "passive"))
      (node (ref "C18") (pin "1") (pinfunction "1_1") (pintype "passive"))
      (node (ref "C19") (pin "1") (pinfunction "1_1") (pintype "passive"))
      (node (ref "C2") (pin "1") (pinfunction "1_1") (pintype "passive"))
      (node (ref "C20") (pin "1") (pinfunction "1_1") (pintype "passive"))
      (node (ref "C3") (pin "1") (pinfunction "1_1") (pintype "passive"))
      (node (ref "C4") (pin "2") (pinfunction "K_2") (pintype "passive"))
      (node (ref "C5") (pin "1") (pinfunction "1_1") (pintype "passive"))
      (node (ref "C7") (pin "2") (pinfunction "K_2") (pintype "passive"))
      (node (ref "C8") (pin "1") (pinfunction "1_1") (pintype "passive"))
      (node (ref "C9") (pin "1") (pinfunction "1_1") (pintype "passive"))
      (node (ref "D1") (pin "2") (pinfunction "A_2") (pintype "passive"))
      (node (ref "FPC1") (pin "20") (pinfunction "20_20") (pintype "passive"))
      (node (ref "JP1") (pin "50") (pinfunction "50_50") (pintype "passive"))
      (node (ref "JP2") (pin "1") (pinfunction "1_1") (pintype "passive"))
      (node (ref "JP2") (pin "49") (pinfunction "49_49") (pintype "passive"))
      (node (ref "JP3") (pin "2") (pinfunction "2_2") (pintype "passive"))
      (node (ref "JP4") (pin "1") (pinfunction "1_1") (pintype "passive"))
      (node (ref "JP5") (pin "21") (pinfunction "21_21") (pintype "passive"))
      (node (ref "JP5") (pin "22") (pinfunction "22_22") (pintype "passive"))
      (node (ref "R4") (pin "1") (pinfunction "1_1") (pintype "passive"))
      (node (ref "R8") (pin "2") (pinfunction "2_2") (pintype "passive"))
      (node (ref "SW1") (pin "2") (pinfunction "B_2") (pintype "passive"))
      (node (ref "U1") (pin "3") (pinfunction "GND_3") (pintype "passive"))
      (node (ref "U3") (pin "15") (pinfunction "GND_15") (pintype "power_in"))
      (node (ref "U4") (pin "5") (pinfunction "GND_5") (pintype "passive"))
      (node (ref "U5") (pin "1") (pinfunction "GND_1") (pintype "passive"))
      (node (ref "U6") (pin "6") (pinfunction "GND_6") (pintype "passive"))
      (node (ref "U6") (pin "9") (pinfunction "PowerPAD_9") (pintype "passive"))
      (node (ref "USB") (pin "5") (pinfunction "GND_5") (pintype "passive"))
    )
    (net (code "93") (name "Net-(D1-K)") (class "Default")
      (node (ref "C6") (pin "1") (pinfunction "1_1") (pintype "passive"))
      (node (ref "D1") (pin "1") (pinfunction "K_1") (pintype "passive"))
      (node (ref "L1") (pin "2") (pinfunction "2_2") (pintype "passive"))
      (node (ref "U6") (pin "8") (pinfunction "PH_8") (pintype "passive"))
    )
    (net (code "94") (name "Net-(RX-K)") (class "Default")
      (node (ref "R2") (pin "1") (pinfunction "1_1") (pintype "passive"))
      (node (ref "RX") (pin "1") (pinfunction "K_1") (pintype "passive"))
    )
    (net (code "95") (name "Net-(TX-K)") (class "Default")
      (node (ref "R1") (pin "1") (pinfunction "1_1") (pintype "passive"))
      (node (ref "TX") (pin "1") (pinfunction "K_1") (pintype "passive"))
    )
    (net (code "96") (name "Net-(U1-V3)") (class "Default")
      (node (ref "C1") (pin "2") (pinfunction "2_2") (pintype "passive"))
      (node (ref "U1") (pin "8") (pinfunction "V3_8") (pintype "passive"))
    )
    (net (code "97") (name "Net-(U3-C1+)") (class "Default")
      (node (ref "C11") (pin "2") (pinfunction "2_2") (pintype "passive"))
      (node (ref "U3") (pin "1") (pinfunction "C1+_1") (pintype "passive"))
    )
    (net (code "98") (name "Net-(U3-C1-)") (class "Default")
      (node (ref "C11") (pin "1") (pinfunction "1_1") (pintype "passive"))
      (node (ref "U3") (pin "3") (pinfunction "C1-_3") (pintype "passive"))
    )
    (net (code "99") (name "Net-(U3-C2+)") (class "Default")
      (node (ref "C12") (pin "1") (pinfunction "1_1") (pintype "passive"))
      (node (ref "U3") (pin "4") (pinfunction "C2+_4") (pintype "passive"))
    )
    (net (code "100") (name "Net-(U3-C2-)") (class "Default")
      (node (ref "C12") (pin "2") (pinfunction "2_2") (pintype "passive"))
      (node (ref "U3") (pin "5") (pinfunction "C2-_5") (pintype "passive"))
    )
    (net (code "101") (name "Net-(U3-V+)") (class "Default")
      (node (ref "C13") (pin "1") (pinfunction "1_1") (pintype "passive"))
      (node (ref "U3") (pin "2") (pinfunction "V+_2") (pintype "power_in"))
    )
    (net (code "102") (name "Net-(U3-V-)") (class "Default")
      (node (ref "C15") (pin "1") (pinfunction "1_1") (pintype "passive"))
      (node (ref "U3") (pin "6") (pinfunction "V-_6") (pintype "power_in"))
    )
    (net (code "103") (name "Net-(U6-BOOT)") (class "Default")
      (node (ref "C6") (pin "2") (pinfunction "2_2") (pintype "passive"))
      (node (ref "U6") (pin "1") (pinfunction "BOOT_1") (pintype "passive"))
    )
    (net (code "104") (name "Net-(U6-VSENSE)") (class "Default")
      (node (ref "R3") (pin "1") (pinfunction "1_1") (pintype "passive"))
      (node (ref "R4") (pin "2") (pinfunction "2_2") (pintype "passive"))
      (node (ref "U6") (pin "4") (pinfunction "VSENSE_4") (pintype "passive"))
    )
    (net (code "105") (name "unconnected-(FPC1-Pad21)") (class "Default")
      (node (ref "FPC1") (pin "21") (pinfunction "21_21") (pintype "passive+no_connect"))
    )
    (net (code "106") (name "unconnected-(FPC1-Pad22)") (class "Default")
      (node (ref "FPC1") (pin "22") (pinfunction "22_22") (pintype "passive+no_connect"))
    )
    (net (code "107") (name "unconnected-(JP1-Pad42)") (class "Default")
      (node (ref "JP1") (pin "42") (pinfunction "42_42") (pintype "passive+no_connect"))
    )
    (net (code "108") (name "unconnected-(JP1-Pad43)") (class "Default")
      (node (ref "JP1") (pin "43") (pinfunction "43_43") (pintype "passive+no_connect"))
    )
    (net (code "109") (name "unconnected-(JP1-Pad44)") (class "Default")
      (node (ref "JP1") (pin "44") (pinfunction "44_44") (pintype "passive+no_connect"))
    )
    (net (code "110") (name "unconnected-(JP1-Pad45)") (class "Default")
      (node (ref "JP1") (pin "45") (pinfunction "45_45") (pintype "passive+no_connect"))
    )
    (net (code "111") (name "unconnected-(JP1-Pad46)") (class "Default")
      (node (ref "JP1") (pin "46") (pinfunction "46_46") (pintype "passive+no_connect"))
    )
    (net (code "112") (name "unconnected-(JP1-Pad47)") (class "Default")
      (node (ref "JP1") (pin "47") (pinfunction "47_47") (pintype "passive+no_connect"))
    )
    (net (code "113") (name "unconnected-(JP1-Pad48)") (class "Default")
      (node (ref "JP1") (pin "48") (pinfunction "48_48") (pintype "passive+no_connect"))
    )
    (net (code "114") (name "unconnected-(JP1-Pad49)") (class "Default")
      (node (ref "JP1") (pin "49") (pinfunction "49_49") (pintype "passive+no_connect"))
    )
    (net (code "115") (name "unconnected-(JP2-Pad2)") (class "Default")
      (node (ref "JP2") (pin "2") (pinfunction "2_2") (pintype "passive+no_connect"))
    )
    (net (code "116") (name "unconnected-(JP2-Pad3)") (class "Default")
      (node (ref "JP2") (pin "3") (pinfunction "3_3") (pintype "passive+no_connect"))
    )
    (net (code "117") (name "unconnected-(JP2-Pad4)") (class "Default")
      (node (ref "JP2") (pin "4") (pinfunction "4_4") (pintype "passive+no_connect"))
    )
    (net (code "118") (name "unconnected-(JP2-Pad5)") (class "Default")
      (node (ref "JP2") (pin "5") (pinfunction "5_5") (pintype "passive+no_connect"))
    )
    (net (code "119") (name "unconnected-(JP2-Pad6)") (class "Default")
      (node (ref "JP2") (pin "6") (pinfunction "6_6") (pintype "passive+no_connect"))
    )
    (net (code "120") (name "unconnected-(JP2-Pad7)") (class "Default")
      (node (ref "JP2") (pin "7") (pinfunction "7_7") (pintype "passive+no_connect"))
    )
    (net (code "121") (name "unconnected-(U1-RTS#-Pad4)") (class "Default")
      (node (ref "U1") (pin "4") (pinfunction "RTS#_4") (pintype "passive"))
    )
    (net (code "122") (name "unconnected-(U3-R2IN-Pad8)") (class "Default")
      (node (ref "U3") (pin "8") (pinfunction "R2IN_8") (pintype "input+no_connect"))
    )
    (net (code "123") (name "unconnected-(U3-R2OUT-Pad9)") (class "Default")
      (node (ref "U3") (pin "9") (pinfunction "R2OUT_9") (pintype "output+no_connect"))
    )
    (net (code "124") (name "unconnected-(U3-T2IN-Pad10)") (class "Default")
      (node (ref "U3") (pin "10") (pinfunction "T2IN_10") (pintype "input+no_connect"))
    )
    (net (code "125") (name "unconnected-(U3-T2OUT-Pad7)") (class "Default")
      (node (ref "U3") (pin "7") (pinfunction "T2OUT_7") (pintype "output+no_connect"))
    )
    (net (code "126") (name "unconnected-(U6-ENA-Pad5)") (class "Default")
      (node (ref "U6") (pin "5") (pinfunction "ENA_5") (pintype "passive"))
    )
    (net (code "127") (name "unconnected-(U6-NC-Pad2)") (class "Default")
      (node (ref "U6") (pin "2") (pinfunction "NC_2") (pintype "passive"))
    )
    (net (code "128") (name "unconnected-(U6-NC-Pad3)") (class "Default")
      (node (ref "U6") (pin "3") (pinfunction "NC_3") (pintype "passive"))
    )
    (net (code "129") (name "unconnected-(USB-ID-Pad4)") (class "Default")
      (node (ref "USB") (pin "4") (pinfunction "ID_4") (pintype "passive"))
    )
  )
)
